# LightSensor.net
KiCad netlist of a schematic drawn in EAGLE
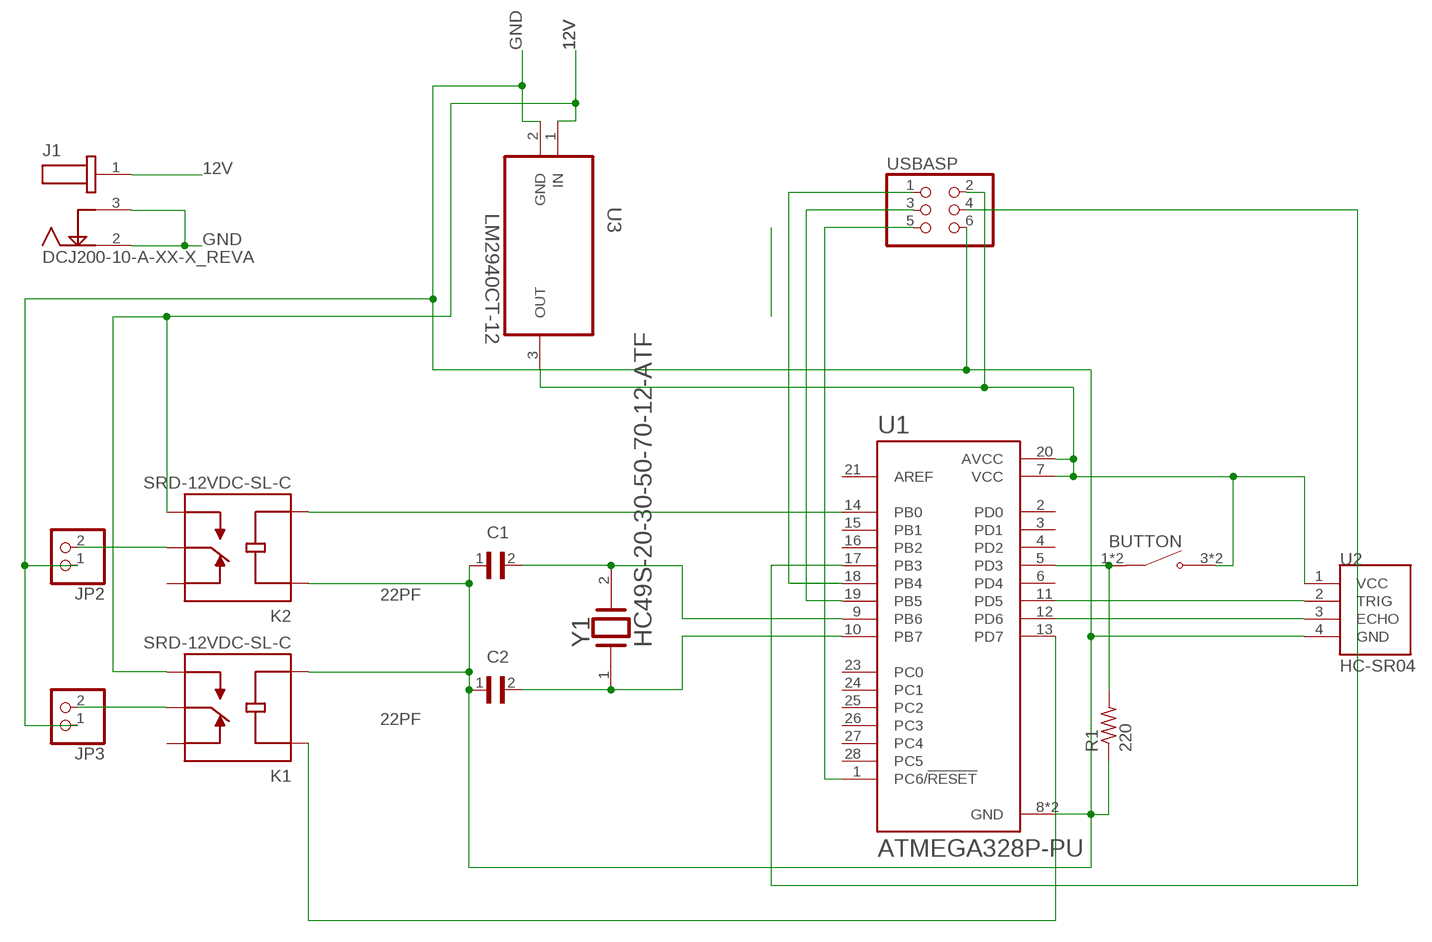
[diagram p0: schematic, sheet 1]

(export (version "E")
  (design (tool "Eeschema 10.0.6"))
  (components
    (comp (ref "C1")
      (value "22PF")
      (footprint "eagle-import:CAP_DE21XSA220KN3AX02F")
      (fields (field (name "MF") "Murata Electronics") (field (name "MP") "DE21XSA220KN3AX02F"))
      (libsource (lib "eagle-import") (part "DE21XSA220KN3AX02F"))
    )
    (comp (ref "C2")
      (value "22PF")
      (footprint "eagle-import:CAP_DE21XSA220KN3AX02F")
      (fields (field (name "MF") "Murata Electronics") (field (name "MP") "DE21XSA220KN3AX02F"))
      (libsource (lib "eagle-import") (part "DE21XSA220KN3AX02F"))
    )
    (comp (ref "J1")
      (value "DCJ200-10-A-XX-X_REVA")
      (footprint "eagle-import:GCT_DCJ200-10-A-XX-X_REVA")
      (fields (field (name "MF") "Global Connector Technology") (field (name "MP") "DCJ200-10-A-K1-K"))
      (libsource (lib "eagle-import") (part "DCJ200-10-A-XX-X_REVA"))
    )
    (comp (ref "JP2")
      (value "PINHD-1X2")
      (footprint "eagle-import:1X02")
      (libsource (lib "eagle-import") (part "PINHD-1X2"))
    )
    (comp (ref "JP3")
      (value "PINHD-1X2")
      (footprint "eagle-import:1X02")
      (libsource (lib "eagle-import") (part "PINHD-1X2"))
    )
    (comp (ref "K1")
      (value "SRD-12VDC-SL-C")
      (footprint "eagle-import:RELAY_SRD-12VDC-SL-C")
      (fields (field (name "MF") "Songle Relay") (field (name "SPICEPREFIX") "X"))
      (libsource (lib "eagle-import") (part "SRD-12VDC-SL-C"))
    )
    (comp (ref "K2")
      (value "SRD-12VDC-SL-C")
      (footprint "eagle-import:RELAY_SRD-12VDC-SL-C")
      (fields (field (name "MF") "Songle Relay"))
      (libsource (lib "eagle-import") (part "SRD-12VDC-SL-C"))
    )
    (comp (ref "R1")
      (value "220")
      (footprint "eagle-import:0309_12")
      (libsource (lib "eagle-import") (part "R-US_0309/12"))
    )
    (comp (ref "S1")
      (value "BUTTON")
      (footprint "eagle-import:BUTTON")
      (fields (field (name "COMMENT") "1571527-1") (field (name "MF") "TE Connectivity"))
      (libsource (lib "eagle-import") (part "BUTTON"))
    )
    (comp (ref "U1")
      (value "ATMEGA328P-PU")
      (footprint "eagle-import:DIP794W46P254L2967H457Q28B")
      (fields (field (name "MF") "Microchip"))
      (libsource (lib "eagle-import") (part "ATMEGA328P-PU"))
    )
    (comp (ref "U2")
      (value "HC-SR04")
      (footprint "eagle-import:XCVR_HC-SR04")
      (fields (field (name "MF") "OSEPP Electronics") (field (name "SPICEPREFIX") "E"))
      (libsource (lib "eagle-import") (part "HC-SR04"))
    )
    (comp (ref "U3")
      (value "LM2940CT-12")
      (footprint "eagle-import:TO254P470X1016X2222-3P")
      (fields (field (name "MF") "Texas Instruments"))
      (libsource (lib "eagle-import") (part "LM2940CT-12"))
    )
    (comp (ref "USBASP")
      (value "PINHD-2X3")
      (footprint "eagle-import:2X03")
      (libsource (lib "eagle-import") (part "PINHD-2X3"))
    )
    (comp (ref "Y1")
      (value "20MHZ")
      (footprint "eagle-import:MULTICOMP_HC49S-20-30-50-70-12-ATF_0")
      (fields (field (name "MF") "Multicomp") (field (name "MPN") "HC49S-20-30-50-70-12-ATF"))
      (libsource (lib "eagle-import") (part "MULTICOMP_HC49S-20-30-50-70-12-ATFMULTICOMP_HC49S-20-30-50-70-12-ATF_0_0"))
    )
  )
  (nets
    (net (code "1") (name "/12V") (class "Default")
      (node (ref "J1") (pin "1") (pinfunction "1_1") (pintype "passive"))
      (node (ref "K1") (pin "NO") (pinfunction "NO_NO") (pintype "passive"))
      (node (ref "K2") (pin "NO") (pinfunction "NO_NO") (pintype "passive"))
      (node (ref "U3") (pin "1") (pinfunction "IN_1") (pintype "input"))
    )
    (net (code "2") (name "/BUTTON") (class "Default")
      (node (ref "R1") (pin "2") (pinfunction "2_2") (pintype "passive"))
      (node (ref "S1") (pin "1") (pinfunction "COM_1") (pintype "passive"))
      (node (ref "S1") (pin "2") (pinfunction "COM_2") (pintype "passive"))
      (node (ref "U1") (pin "5") (pinfunction "PD3_5") (pintype "bidirectional"))
    )
    (net (code "3") (name "/GND") (class "Default")
      (node (ref "C1") (pin "1") (pinfunction "1_1") (pintype "passive"))
      (node (ref "C2") (pin "1") (pinfunction "1_1") (pintype "passive"))
      (node (ref "J1") (pin "2") (pinfunction "2_2") (pintype "passive"))
      (node (ref "J1") (pin "3") (pinfunction "3_3") (pintype "passive"))
      (node (ref "JP2") (pin "1") (pinfunction "1_1") (pintype "passive"))
      (node (ref "JP3") (pin "1") (pinfunction "1_1") (pintype "passive"))
      (node (ref "K1") (pin "COIL2") (pinfunction "COIL2_COIL2") (pintype "passive"))
      (node (ref "K2") (pin "COIL1") (pinfunction "COIL1_COIL1") (pintype "passive"))
      (node (ref "R1") (pin "1") (pinfunction "1_1") (pintype "passive"))
      (node (ref "U1") (pin "22") (pinfunction "GND_22") (pintype "power_in"))
      (node (ref "U1") (pin "8") (pinfunction "GND_8") (pintype "power_in"))
      (node (ref "U2") (pin "4") (pinfunction "GND_4") (pintype "power_in"))
      (node (ref "U3") (pin "2") (pinfunction "GND_2") (pintype "passive"))
      (node (ref "USBASP") (pin "6") (pinfunction "6_6") (pintype "passive"))
    )
    (net (code "4") (name "Net-(JP2-Pad2)") (class "Default")
      (node (ref "JP2") (pin "2") (pinfunction "2_2") (pintype "passive"))
      (node (ref "K2") (pin "COM") (pinfunction "COM_COM") (pintype "passive"))
    )
    (net (code "5") (name "Net-(JP3-Pad2)") (class "Default")
      (node (ref "JP3") (pin "2") (pinfunction "2_2") (pintype "passive"))
      (node (ref "K1") (pin "COM") (pinfunction "COM_COM") (pintype "passive"))
    )
    (net (code "6") (name "Net-(U1-AVCC)") (class "Default")
      (node (ref "S1") (pin "3") (pinfunction "NO_3") (pintype "passive"))
      (node (ref "S1") (pin "4") (pinfunction "NO_4") (pintype "passive"))
      (node (ref "U1") (pin "20") (pinfunction "AVCC_20") (pintype "power_in"))
      (node (ref "U1") (pin "7") (pinfunction "VCC_7") (pintype "power_in"))
      (node (ref "U2") (pin "1") (pinfunction "VCC_1") (pintype "power_in"))
      (node (ref "U3") (pin "3") (pinfunction "OUT_3") (pintype "output"))
      (node (ref "USBASP") (pin "2") (pinfunction "2_2") (pintype "passive"))
    )
    (net (code "7") (name "Net-(U1-PB0)") (class "Default")
      (node (ref "K2") (pin "COIL2") (pinfunction "COIL2_COIL2") (pintype "passive"))
      (node (ref "U1") (pin "14") (pinfunction "PB0_14") (pintype "bidirectional"))
    )
    (net (code "8") (name "Net-(U1-PB3)") (class "Default")
      (node (ref "U1") (pin "17") (pinfunction "PB3_17") (pintype "bidirectional"))
      (node (ref "USBASP") (pin "4") (pinfunction "4_4") (pintype "passive"))
    )
    (net (code "9") (name "Net-(U1-PB4)") (class "Default")
      (node (ref "U1") (pin "18") (pinfunction "PB4_18") (pintype "bidirectional"))
      (node (ref "USBASP") (pin "1") (pinfunction "1_1") (pintype "passive"))
    )
    (net (code "10") (name "Net-(U1-PB5)") (class "Default")
      (node (ref "U1") (pin "19") (pinfunction "PB5_19") (pintype "bidirectional"))
      (node (ref "USBASP") (pin "3") (pinfunction "3_3") (pintype "passive"))
    )
    (net (code "11") (name "Net-(U1-PB6)") (class "Default")
      (node (ref "C1") (pin "2") (pinfunction "2_2") (pintype "passive"))
      (node (ref "U1") (pin "9") (pinfunction "PB6_9") (pintype "bidirectional"))
      (node (ref "Y1") (pin "2") (pinfunction "2_2") (pintype "bidirectional"))
    )
    (net (code "12") (name "Net-(U1-PB7)") (class "Default")
      (node (ref "C2") (pin "2") (pinfunction "2_2") (pintype "passive"))
      (node (ref "U1") (pin "10") (pinfunction "PB7_10") (pintype "bidirectional"))
      (node (ref "Y1") (pin "1") (pinfunction "1_1") (pintype "bidirectional"))
    )
    (net (code "13") (name "Net-(U1-PC6{slash}~{RESET})") (class "Default")
      (node (ref "U1") (pin "1") (pinfunction "PC6/~{RESET}_1") (pintype "bidirectional"))
      (node (ref "USBASP") (pin "5") (pinfunction "5_5") (pintype "passive"))
    )
    (net (code "14") (name "Net-(U1-PD5)") (class "Default")
      (node (ref "U1") (pin "11") (pinfunction "PD5_11") (pintype "bidirectional"))
      (node (ref "U2") (pin "2") (pinfunction "TRIG_2") (pintype "bidirectional"))
    )
    (net (code "15") (name "Net-(U1-PD6)") (class "Default")
      (node (ref "U1") (pin "12") (pinfunction "PD6_12") (pintype "bidirectional"))
      (node (ref "U2") (pin "3") (pinfunction "ECHO_3") (pintype "bidirectional"))
    )
    (net (code "16") (name "Net-(U1-PD7)") (class "Default")
      (node (ref "K1") (pin "COIL1") (pinfunction "COIL1_COIL1") (pintype "passive"))
      (node (ref "U1") (pin "13") (pinfunction "PD7_13") (pintype "bidirectional"))
    )
    (net (code "17") (name "unconnected-(K1-PadNC)") (class "Default")
      (node (ref "K1") (pin "NC") (pinfunction "NC_NC") (pintype "passive"))
    )
    (net (code "18") (name "unconnected-(K2-PadNC)") (class "Default")
      (node (ref "K2") (pin "NC") (pinfunction "NC_NC") (pintype "passive"))
    )
    (net (code "19") (name "unconnected-(U1-AREF-Pad21)") (class "Default")
      (node (ref "U1") (pin "21") (pinfunction "AREF_21") (pintype "input"))
    )
    (net (code "20") (name "unconnected-(U1-PB1-Pad15)") (class "Default")
      (node (ref "U1") (pin "15") (pinfunction "PB1_15") (pintype "bidirectional"))
    )
    (net (code "21") (name "unconnected-(U1-PB2-Pad16)") (class "Default")
      (node (ref "U1") (pin "16") (pinfunction "PB2_16") (pintype "bidirectional"))
    )
    (net (code "22") (name "unconnected-(U1-PC0-Pad23)") (class "Default")
      (node (ref "U1") (pin "23") (pinfunction "PC0_23") (pintype "bidirectional"))
    )
    (net (code "23") (name "unconnected-(U1-PC1-Pad24)") (class "Default")
      (node (ref "U1") (pin "24") (pinfunction "PC1_24") (pintype "bidirectional"))
    )
    (net (code "24") (name "unconnected-(U1-PC2-Pad25)") (class "Default")
      (node (ref "U1") (pin "25") (pinfunction "PC2_25") (pintype "bidirectional"))
    )
    (net (code "25") (name "unconnected-(U1-PC3-Pad26)") (class "Default")
      (node (ref "U1") (pin "26") (pinfunction "PC3_26") (pintype "bidirectional"))
    )
    (net (code "26") (name "unconnected-(U1-PC4-Pad27)") (class "Default")
      (node (ref "U1") (pin "27") (pinfunction "PC4_27") (pintype "bidirectional"))
    )
    (net (code "27") (name "unconnected-(U1-PC5-Pad28)") (class "Default")
      (node (ref "U1") (pin "28") (pinfunction "PC5_28") (pintype "bidirectional"))
    )
    (net (code "28") (name "unconnected-(U1-PD0-Pad2)") (class "Default")
      (node (ref "U1") (pin "2") (pinfunction "PD0_2") (pintype "bidirectional"))
    )
    (net (code "29") (name "unconnected-(U1-PD1-Pad3)") (class "Default")
      (node (ref "U1") (pin "3") (pinfunction "PD1_3") (pintype "bidirectional"))
    )
    (net (code "30") (name "unconnected-(U1-PD2-Pad4)") (class "Default")
      (node (ref "U1") (pin "4") (pinfunction "PD2_4") (pintype "bidirectional"))
    )
    (net (code "31") (name "unconnected-(U1-PD4-Pad6)") (class "Default")
      (node (ref "U1") (pin "6") (pinfunction "PD4_6") (pintype "bidirectional"))
    )
  )
)
